# Bond.net
KiCad netlist of a schematic drawn in EAGLE
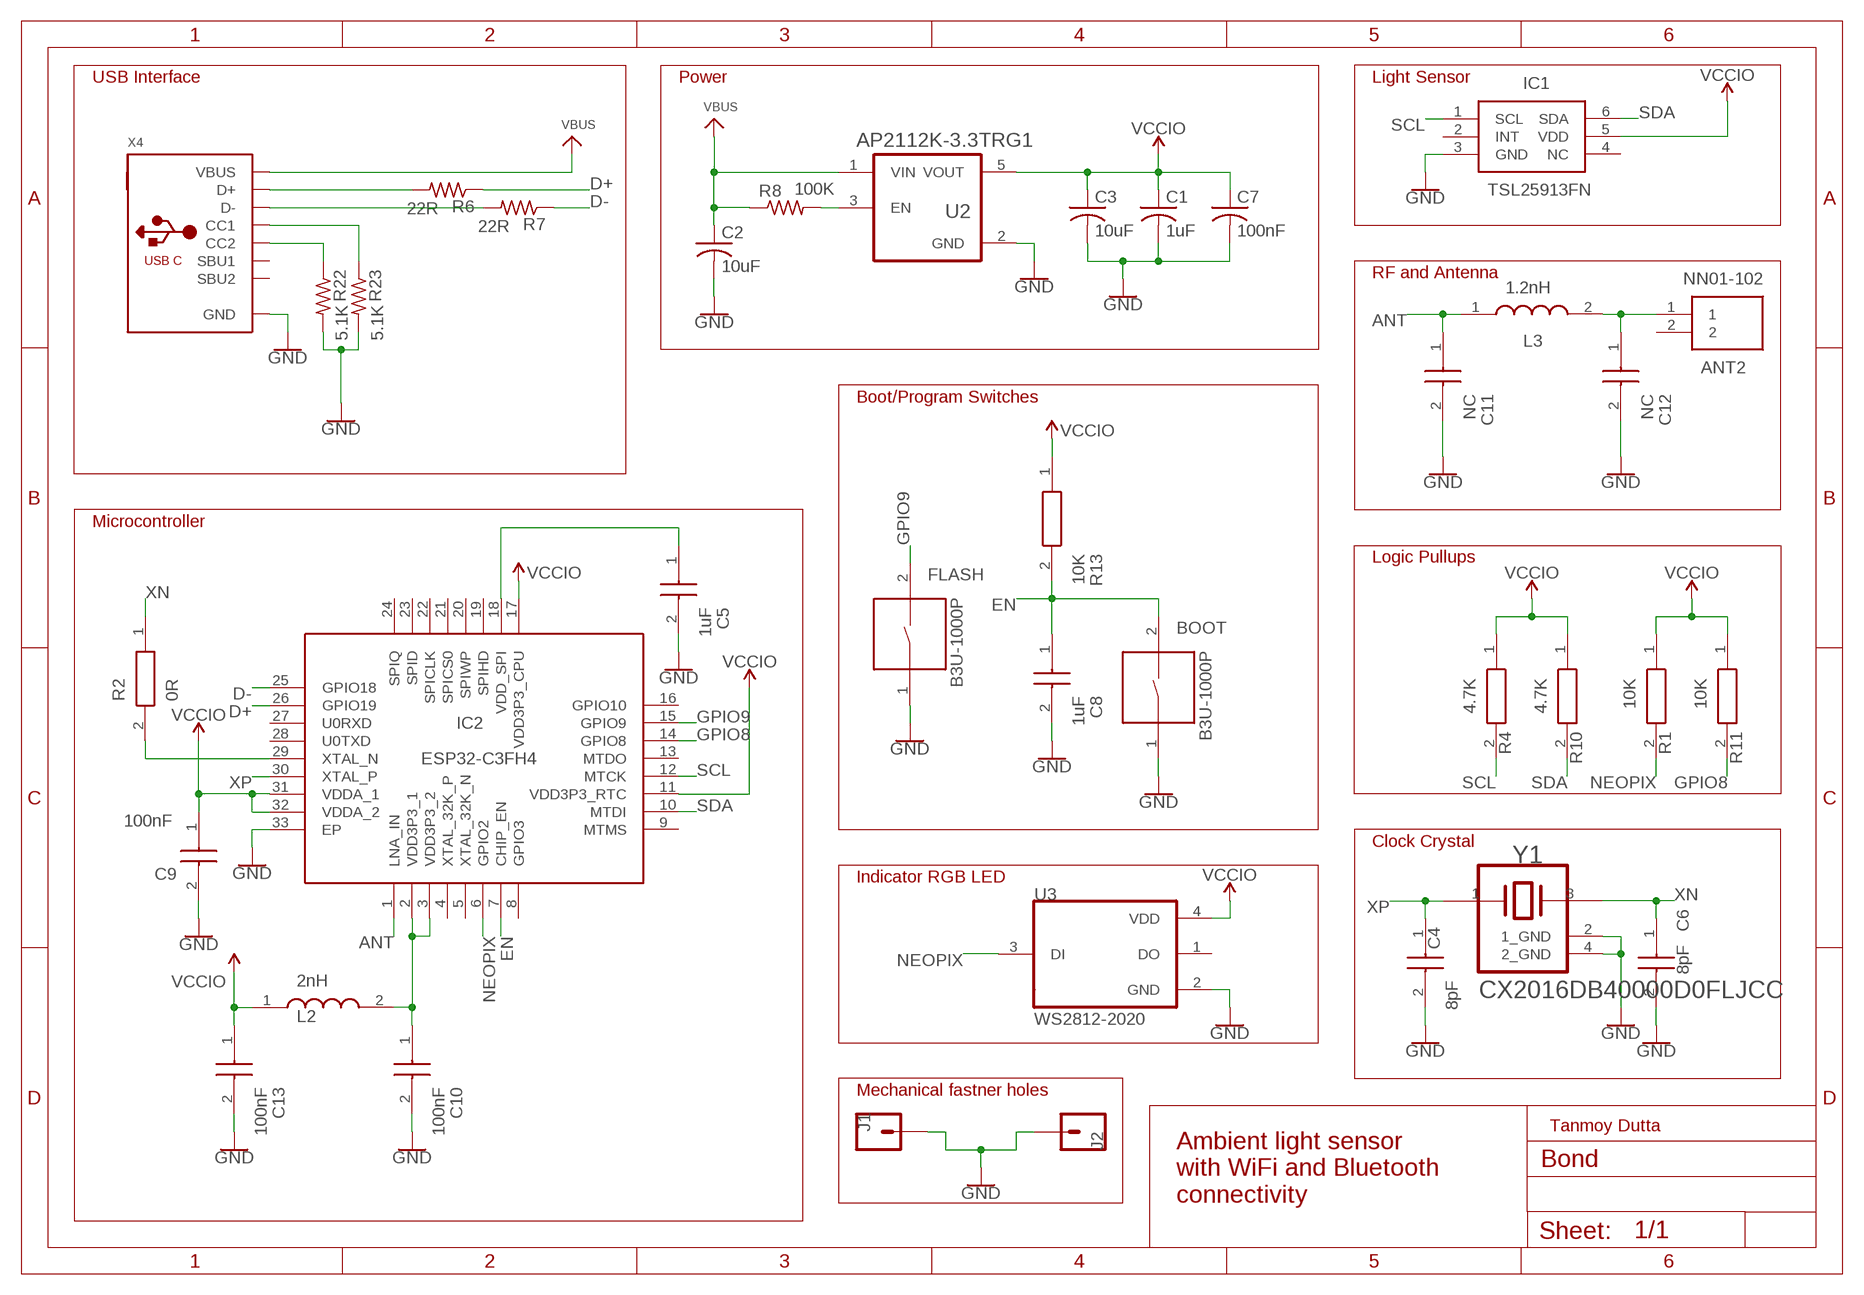
[diagram p0: schematic, sheet 1]

(export (version "E")
  (design (tool "Eeschema 10.0.6"))
  (components
    (comp (ref "ANT2")
      (value "NN01-102")
      (footprint "eagle-import:NN01102")
      (fields (field (name "MOUSER_PART_NUMBER") "128-NN01-102"))
      (libsource (lib "eagle-import") (part "NN01-102"))
    )
    (comp (ref "BOOT")
      (value "B3U-1000P")
      (footprint "eagle-import:SW_B3U-1000P")
      (fields (field (name "MF") "Omron"))
      (libsource (lib "eagle-import") (part "B3U-1000P"))
    )
    (comp (ref "C1")
      (value "1uF")
      (footprint "eagle-import:C0402")
      (fields (field (name "SPICEPREFIX") "C"))
      (libsource (lib "eagle-import") (part "C-USC0402"))
    )
    (comp (ref "C2")
      (value "10uF")
      (footprint "eagle-import:C0402")
      (fields (field (name "SPICEPREFIX") "C"))
      (libsource (lib "eagle-import") (part "C-USC0402"))
    )
    (comp (ref "C3")
      (value "10uF")
      (footprint "eagle-import:C0402")
      (fields (field (name "SPICEPREFIX") "C"))
      (libsource (lib "eagle-import") (part "C-USC0402"))
    )
    (comp (ref "C4")
      (value "8pF")
      (footprint "eagle-import:CAPC1005X55N")
      (fields
        (field (name "MANUFACTURER_PART_NUMBER") "GJM1555C1H120JB01J")
        (field (name "MOUSER_PART_NUMBER") "81-GJM1555C1H120JB1J")
      )
      (libsource (lib "eagle-import") (part "GJM1555C1H120JB01J"))
    )
    (comp (ref "C5")
      (value "1uF")
      (footprint "eagle-import:CAPC1005X55N")
      (fields
        (field (name "MANUFACTURER_PART_NUMBER") "GJM1555C1H120JB01J")
        (field (name "MOUSER_PART_NUMBER") "81-GJM1555C1H120JB1J")
      )
      (libsource (lib "eagle-import") (part "GJM1555C1H120JB01J"))
    )
    (comp (ref "C6")
      (value "8pF")
      (footprint "eagle-import:CAPC1005X55N")
      (fields
        (field (name "MANUFACTURER_PART_NUMBER") "GJM1555C1H120JB01J")
        (field (name "MOUSER_PART_NUMBER") "81-GJM1555C1H120JB1J")
      )
      (libsource (lib "eagle-import") (part "GJM1555C1H120JB01J"))
    )
    (comp (ref "C7")
      (value "100nF")
      (footprint "eagle-import:C0402")
      (fields (field (name "SPICEPREFIX") "C"))
      (libsource (lib "eagle-import") (part "C-USC0402"))
    )
    (comp (ref "C8")
      (value "1uF")
      (footprint "eagle-import:CAPC1005X55N")
      (fields
        (field (name "MANUFACTURER_PART_NUMBER") "GJM1555C1H120JB01J")
        (field (name "MOUSER_PART_NUMBER") "81-GJM1555C1H120JB1J")
      )
      (libsource (lib "eagle-import") (part "GJM1555C1H120JB01J"))
    )
    (comp (ref "C9")
      (value "100nF")
      (footprint "eagle-import:CAPC1005X55N")
      (fields
        (field (name "MANUFACTURER_PART_NUMBER") "GJM1555C1H120JB01J")
        (field (name "MOUSER_PART_NUMBER") "81-GJM1555C1H120JB1J")
      )
      (libsource (lib "eagle-import") (part "GJM1555C1H120JB01J"))
    )
    (comp (ref "C10")
      (value "100nF")
      (footprint "eagle-import:CAPC1005X55N")
      (fields
        (field (name "MANUFACTURER_PART_NUMBER") "GJM1555C1H120JB01J")
        (field (name "MOUSER_PART_NUMBER") "81-GJM1555C1H120JB1J")
      )
      (libsource (lib "eagle-import") (part "GJM1555C1H120JB01J"))
    )
    (comp (ref "C11")
      (value "NC")
      (footprint "eagle-import:CAPC1005X55N")
      (fields
        (field (name "MANUFACTURER_PART_NUMBER") "GJM1555C1H120JB01J")
        (field (name "MOUSER_PART_NUMBER") "81-GJM1555C1H120JB1J")
      )
      (libsource (lib "eagle-import") (part "GJM1555C1H120JB01J"))
    )
    (comp (ref "C12")
      (value "NC")
      (footprint "eagle-import:CAPC1005X55N")
      (fields
        (field (name "MANUFACTURER_PART_NUMBER") "GJM1555C1H120JB01J")
        (field (name "MOUSER_PART_NUMBER") "81-GJM1555C1H120JB1J")
      )
      (libsource (lib "eagle-import") (part "GJM1555C1H120JB01J"))
    )
    (comp (ref "C13")
      (value "100nF")
      (footprint "eagle-import:CAPC1005X55N")
      (fields
        (field (name "MANUFACTURER_PART_NUMBER") "GJM1555C1H120JB01J")
        (field (name "MOUSER_PART_NUMBER") "81-GJM1555C1H120JB1J")
      )
      (libsource (lib "eagle-import") (part "GJM1555C1H120JB01J"))
    )
    (comp (ref "FLASH")
      (value "B3U-1000P")
      (footprint "eagle-import:SW_B3U-1000P")
      (fields (field (name "MF") "Omron"))
      (libsource (lib "eagle-import") (part "B3U-1000P"))
    )
    (comp (ref "IC1")
      (value "TSL25913FN")
      (footprint "eagle-import:TSL25913FN")
      (fields (field (name "MOUSER_PART_NUMBER") "985-TSL25913FN") (field (name "SPICEPREFIX") "X"))
      (libsource (lib "eagle-import") (part "TSL25913FN"))
    )
    (comp (ref "IC2")
      (value "ESP32-C3FH4")
      (footprint "eagle-import:QFN50P500X500X90-33N")
      (fields (field (name "MOUSER_PART_NUMBER") "356-ESP32-C3FH4"))
      (libsource (lib "eagle-import") (part "ESP32-C3FH4"))
    )
    (comp (ref "J1")
      (value "CONN_01PTH_2MM")
      (footprint "eagle-import:1X01_2MM")
      (libsource (lib "eagle-import") (part "CONN_01PTH_2MM"))
    )
    (comp (ref "J2")
      (value "CONN_01PTH_2MM")
      (footprint "eagle-import:1X01_2MM")
      (libsource (lib "eagle-import") (part "CONN_01PTH_2MM"))
    )
    (comp (ref "L2")
      (value "2nH")
      (footprint "eagle-import:LQG15WH0N7B02D")
      (fields
        (field (name "ARROW_PART_NUMBER") "LQG15HH2N0S02D")
        (field (name "MOUSER_PART_NUMBER") "81-LQG15HH2N0S02D")
      )
      (libsource (lib "eagle-import") (part "LQG15HH2N0S02D"))
    )
    (comp (ref "L3")
      (value "1.2nH")
      (footprint "eagle-import:LQW15CNR20J00B")
      (fields (field (name "MANUFACTURER_PART_NUMBER") "LQW15AN1N6C0ZD"))
      (libsource (lib "eagle-import") (part "LQW15AN1N6C0ZD"))
    )
    (comp (ref "R1")
      (value "10K")
      (footprint "eagle-import:RESC1005X40N")
      (fields
        (field (name "ARROW_PART_NUMBER") "CRCW04020000Z0EE")
        (field (name "MOUSER_PART_NUMBER") "71-CRCW04020000Z0EE")
      )
      (libsource (lib "eagle-import") (part "CRCW04020000Z0EE"))
    )
    (comp (ref "R2")
      (value "0R")
      (footprint "eagle-import:RESC1005X40N")
      (fields
        (field (name "ARROW_PART_NUMBER") "CRCW04020000Z0EE")
        (field (name "MOUSER_PART_NUMBER") "71-CRCW04020000Z0EE")
      )
      (libsource (lib "eagle-import") (part "CRCW04020000Z0EE"))
    )
    (comp (ref "R4")
      (value "4.7K")
      (footprint "eagle-import:RESC1005X40N")
      (fields
        (field (name "ARROW_PART_NUMBER") "CRCW04020000Z0EE")
        (field (name "MOUSER_PART_NUMBER") "71-CRCW04020000Z0EE")
      )
      (libsource (lib "eagle-import") (part "CRCW04020000Z0EE"))
    )
    (comp (ref "R6")
      (value "22R")
      (footprint "eagle-import:R0402")
      (fields (field (name "SPICEPREFIX") "R"))
      (libsource (lib "eagle-import") (part "R-US_R0402"))
    )
    (comp (ref "R7")
      (value "22R")
      (footprint "eagle-import:R0402")
      (fields (field (name "SPICEPREFIX") "R"))
      (libsource (lib "eagle-import") (part "R-US_R0402"))
    )
    (comp (ref "R8")
      (value "100K")
      (footprint "eagle-import:R0402")
      (fields (field (name "SPICEPREFIX") "R"))
      (libsource (lib "eagle-import") (part "R-US_R0402"))
    )
    (comp (ref "R10")
      (value "4.7K")
      (footprint "eagle-import:RESC1005X40N")
      (fields
        (field (name "ARROW_PART_NUMBER") "CRCW04020000Z0EE")
        (field (name "MOUSER_PART_NUMBER") "71-CRCW04020000Z0EE")
      )
      (libsource (lib "eagle-import") (part "CRCW04020000Z0EE"))
    )
    (comp (ref "R11")
      (value "10K")
      (footprint "eagle-import:RESC1005X40N")
      (fields
        (field (name "ARROW_PART_NUMBER") "CRCW04020000Z0EE")
        (field (name "MOUSER_PART_NUMBER") "71-CRCW04020000Z0EE")
      )
      (libsource (lib "eagle-import") (part "CRCW04020000Z0EE"))
    )
    (comp (ref "R13")
      (value "10K")
      (footprint "eagle-import:RESC1005X40N")
      (fields
        (field (name "ARROW_PART_NUMBER") "CRCW04020000Z0EE")
        (field (name "MOUSER_PART_NUMBER") "71-CRCW04020000Z0EE")
      )
      (libsource (lib "eagle-import") (part "CRCW04020000Z0EE"))
    )
    (comp (ref "R22")
      (value "5.1K")
      (footprint "eagle-import:R0402")
      (fields (field (name "SPICEPREFIX") "R"))
      (libsource (lib "eagle-import") (part "R-US_R0402"))
    )
    (comp (ref "R23")
      (value "5.1K")
      (footprint "eagle-import:R0402")
      (fields (field (name "SPICEPREFIX") "R"))
      (libsource (lib "eagle-import") (part "R-US_R0402"))
    )
    (comp (ref "U2")
      (value "AP2112K-3.3TRG1")
      (footprint "eagle-import:SOT95P285X140-5N")
      (fields (field (name "MF") "Diodes Inc.") (field (name "SPICEPREFIX") "E"))
      (libsource (lib "eagle-import") (part "AP2112K-3.3TRG1"))
    )
    (comp (ref "U3")
      (value "WS2812-2020")
      (footprint "eagle-import:LED_WS2812-2020")
      (fields (field (name "MF") "Worldsemi"))
      (libsource (lib "eagle-import") (part "WS2812-2020"))
    )
    (comp (ref "X4")
      (value "MICROBUILDER_USB_C")
      (footprint "eagle-import:MICROBUILDER_USB_C_CUSB31-CFM2AX-01-X")
      (fields (field (name "SPICEPREFIX") "X"))
      (libsource (lib "eagle-import") (part "MICROBUILDER_USB_C"))
    )
    (comp (ref "Y1")
      (value "40MHz")
      (footprint "eagle-import:KYOCERA_INTERNATIONAL_INC._ELECTRONIC_COMPONENTS_CX2016DB40000D0FLJCC_0")
      (fields
        (field (name "DIGIKEY_PART_NUMBER") "1253-1120-1-ND")
        (field (name "MF") "Kyocera International Inc. Electronic Components")
        (field (name "MOUSER_PART_NUMBER") "581-CX2016DB40DFLJCC")
      )
      (libsource (lib "eagle-import") (part "KYOCERA_INTERNATIONAL_INC._ELECTRONIC_COMPONENTS_CX2016DB40000D0FLJCCKYOCERA_INTERNATIONAL_INC._ELECTRONIC_COMPONENTS_CX2016DB40000D0FLJCC_0_0"))
    )
  )
  (nets
    (net (code "1") (name "/ANT") (class "Default")
      (node (ref "C11") (pin "1") (pinfunction "1_1") (pintype "bidirectional"))
      (node (ref "IC2") (pin "1") (pinfunction "LNA_IN_1") (pintype "bidirectional"))
      (node (ref "L3") (pin "1") (pinfunction "1_1") (pintype "bidirectional"))
    )
    (net (code "2") (name "/D+") (class "Default")
      (node (ref "IC2") (pin "26") (pinfunction "GPIO19_26") (pintype "bidirectional"))
      (node (ref "R6") (pin "1") (pinfunction "1_1") (pintype "passive"))
    )
    (net (code "3") (name "/D-") (class "Default")
      (node (ref "IC2") (pin "25") (pinfunction "GPIO18_25") (pintype "bidirectional"))
      (node (ref "R7") (pin "1") (pinfunction "1_1") (pintype "passive"))
    )
    (net (code "4") (name "/EN") (class "Default")
      (node (ref "BOOT") (pin "2") (pinfunction "2_2") (pintype "passive"))
      (node (ref "C8") (pin "1") (pinfunction "1_1") (pintype "bidirectional"))
      (node (ref "IC2") (pin "7") (pinfunction "CHIP_EN_7") (pintype "bidirectional"))
      (node (ref "R13") (pin "2") (pinfunction "2_2") (pintype "bidirectional"))
    )
    (net (code "5") (name "/GPIO8") (class "Default")
      (node (ref "IC2") (pin "14") (pinfunction "GPIO8_14") (pintype "bidirectional"))
      (node (ref "R11") (pin "2") (pinfunction "2_2") (pintype "bidirectional"))
    )
    (net (code "6") (name "/GPIO9") (class "Default")
      (node (ref "FLASH") (pin "2") (pinfunction "2_2") (pintype "passive"))
      (node (ref "IC2") (pin "15") (pinfunction "GPIO9_15") (pintype "bidirectional"))
    )
    (net (code "7") (name "/NEOPIX") (class "Default")
      (node (ref "IC2") (pin "6") (pinfunction "GPIO2_6") (pintype "bidirectional"))
      (node (ref "R1") (pin "2") (pinfunction "2_2") (pintype "bidirectional"))
      (node (ref "U3") (pin "3") (pinfunction "DI_3") (pintype "input"))
    )
    (net (code "8") (name "/SCL") (class "Default")
      (node (ref "IC1") (pin "1") (pinfunction "SCL_1") (pintype "bidirectional"))
      (node (ref "IC2") (pin "12") (pinfunction "MTCK_12") (pintype "bidirectional"))
      (node (ref "R4") (pin "2") (pinfunction "2_2") (pintype "bidirectional"))
    )
    (net (code "9") (name "/SDA") (class "Default")
      (node (ref "IC1") (pin "6") (pinfunction "SDA_6") (pintype "bidirectional"))
      (node (ref "IC2") (pin "10") (pinfunction "MTDI_10") (pintype "bidirectional"))
      (node (ref "R10") (pin "2") (pinfunction "2_2") (pintype "bidirectional"))
    )
    (net (code "10") (name "/XN") (class "Default")
      (node (ref "C6") (pin "1") (pinfunction "1_1") (pintype "bidirectional"))
      (node (ref "R2") (pin "1") (pinfunction "1_1") (pintype "bidirectional"))
      (node (ref "Y1") (pin "3") (pinfunction "3_3") (pintype "passive"))
    )
    (net (code "11") (name "/XP") (class "Default")
      (node (ref "C4") (pin "1") (pinfunction "1_1") (pintype "bidirectional"))
      (node (ref "IC2") (pin "30") (pinfunction "XTAL_P_30") (pintype "bidirectional"))
      (node (ref "Y1") (pin "1") (pinfunction "1_1") (pintype "passive"))
    )
    (net (code "12") (name "GND") (class "Default")
      (node (ref "BOOT") (pin "1") (pinfunction "1_1") (pintype "passive"))
      (node (ref "C1") (pin "2") (pinfunction "2_2") (pintype "passive"))
      (node (ref "C10") (pin "2") (pinfunction "2_2") (pintype "bidirectional"))
      (node (ref "C11") (pin "2") (pinfunction "2_2") (pintype "bidirectional"))
      (node (ref "C12") (pin "2") (pinfunction "2_2") (pintype "bidirectional"))
      (node (ref "C13") (pin "2") (pinfunction "2_2") (pintype "bidirectional"))
      (node (ref "C2") (pin "2") (pinfunction "2_2") (pintype "passive"))
      (node (ref "C3") (pin "2") (pinfunction "2_2") (pintype "passive"))
      (node (ref "C4") (pin "2") (pinfunction "2_2") (pintype "bidirectional"))
      (node (ref "C5") (pin "2") (pinfunction "2_2") (pintype "bidirectional"))
      (node (ref "C6") (pin "2") (pinfunction "2_2") (pintype "bidirectional"))
      (node (ref "C7") (pin "2") (pinfunction "2_2") (pintype "passive"))
      (node (ref "C8") (pin "2") (pinfunction "2_2") (pintype "bidirectional"))
      (node (ref "C9") (pin "2") (pinfunction "2_2") (pintype "bidirectional"))
      (node (ref "FLASH") (pin "1") (pinfunction "1_1") (pintype "passive"))
      (node (ref "IC1") (pin "3") (pinfunction "GND_3") (pintype "bidirectional"))
      (node (ref "IC2") (pin "33") (pinfunction "EP_33") (pintype "bidirectional"))
      (node (ref "J1") (pin "1") (pinfunction "1_1") (pintype "passive"))
      (node (ref "J2") (pin "1") (pinfunction "1_1") (pintype "passive"))
      (node (ref "R22") (pin "2") (pinfunction "2_2") (pintype "passive"))
      (node (ref "R23") (pin "2") (pinfunction "2_2") (pintype "passive"))
      (node (ref "U2") (pin "2") (pinfunction "GND_2") (pintype "power_in"))
      (node (ref "U3") (pin "2") (pinfunction "GND_2") (pintype "power_in"))
      (node (ref "X4") (pin "A1B12") (pinfunction "GND_A1B12") (pintype "power_in"))
      (node (ref "X4") (pin "B1A12") (pinfunction "GND_B1A12") (pintype "power_in"))
      (node (ref "Y1") (pin "2") (pinfunction "1_GND_2") (pintype "power_in"))
      (node (ref "Y1") (pin "4") (pinfunction "2_GND_4") (pintype "power_in"))
    )
    (net (code "13") (name "Net-(ANT2-Pad1)") (class "Default")
      (node (ref "ANT2") (pin "1") (pinfunction "1_1") (pintype "bidirectional"))
      (node (ref "C12") (pin "1") (pinfunction "1_1") (pintype "bidirectional"))
      (node (ref "L3") (pin "2") (pinfunction "2_2") (pintype "bidirectional"))
    )
    (net (code "14") (name "Net-(IC2-VDD3P3_1)") (class "Default")
      (node (ref "C10") (pin "1") (pinfunction "1_1") (pintype "bidirectional"))
      (node (ref "IC2") (pin "2") (pinfunction "VDD3P3_1_2") (pintype "bidirectional"))
      (node (ref "IC2") (pin "3") (pinfunction "VDD3P3_2_3") (pintype "bidirectional"))
      (node (ref "L2") (pin "2") (pinfunction "2_2") (pintype "bidirectional"))
    )
    (net (code "15") (name "Net-(IC2-VDD_SPI)") (class "Default")
      (node (ref "C5") (pin "1") (pinfunction "1_1") (pintype "bidirectional"))
      (node (ref "IC2") (pin "18") (pinfunction "VDD_SPI_18") (pintype "bidirectional"))
    )
    (net (code "16") (name "Net-(IC2-XTAL_N)") (class "Default")
      (node (ref "IC2") (pin "29") (pinfunction "XTAL_N_29") (pintype "bidirectional"))
      (node (ref "R2") (pin "2") (pinfunction "2_2") (pintype "bidirectional"))
    )
    (net (code "17") (name "Net-(R6-Pad2)") (class "Default")
      (node (ref "R6") (pin "2") (pinfunction "2_2") (pintype "passive"))
      (node (ref "X4") (pin "A6") (pinfunction "D+_A6") (pintype "bidirectional"))
      (node (ref "X4") (pin "B6") (pinfunction "D+_B6") (pintype "bidirectional"))
    )
    (net (code "18") (name "Net-(R7-Pad2)") (class "Default")
      (node (ref "R7") (pin "2") (pinfunction "2_2") (pintype "passive"))
      (node (ref "X4") (pin "A7") (pinfunction "D-_A7") (pintype "bidirectional"))
      (node (ref "X4") (pin "B7") (pinfunction "D-_B7") (pintype "bidirectional"))
    )
    (net (code "19") (name "Net-(U2-EN)") (class "Default")
      (node (ref "R8") (pin "2") (pinfunction "2_2") (pintype "passive"))
      (node (ref "U2") (pin "3") (pinfunction "EN_3") (pintype "input"))
    )
    (net (code "20") (name "Net-(X4-CC1)") (class "Default")
      (node (ref "R23") (pin "1") (pinfunction "1_1") (pintype "passive"))
      (node (ref "X4") (pin "A5") (pinfunction "CC1_A5") (pintype "bidirectional"))
    )
    (net (code "21") (name "Net-(X4-CC2)") (class "Default")
      (node (ref "R22") (pin "1") (pinfunction "1_1") (pintype "passive"))
      (node (ref "X4") (pin "B5") (pinfunction "CC2_B5") (pintype "bidirectional"))
    )
    (net (code "22") (name "VBUS") (class "Default")
      (node (ref "C2") (pin "1") (pinfunction "1_1") (pintype "passive"))
      (node (ref "R8") (pin "1") (pinfunction "1_1") (pintype "passive"))
      (node (ref "U2") (pin "1") (pinfunction "VIN_1") (pintype "power_in"))
      (node (ref "X4") (pin "A4B9") (pinfunction "VBUS_A4B9") (pintype "power_in"))
      (node (ref "X4") (pin "B4A9") (pinfunction "VBUS_B4A9") (pintype "power_in"))
    )
    (net (code "23") (name "VCCIO") (class "Default")
      (node (ref "C1") (pin "1") (pinfunction "1_1") (pintype "passive"))
      (node (ref "C13") (pin "1") (pinfunction "1_1") (pintype "bidirectional"))
      (node (ref "C3") (pin "1") (pinfunction "1_1") (pintype "passive"))
      (node (ref "C7") (pin "1") (pinfunction "1_1") (pintype "passive"))
      (node (ref "C9") (pin "1") (pinfunction "1_1") (pintype "bidirectional"))
      (node (ref "IC1") (pin "5") (pinfunction "VDD_5") (pintype "bidirectional"))
      (node (ref "IC2") (pin "11") (pinfunction "VDD3P3_RTC_11") (pintype "bidirectional"))
      (node (ref "IC2") (pin "17") (pinfunction "VDD3P3_CPU_17") (pintype "bidirectional"))
      (node (ref "IC2") (pin "31") (pinfunction "VDDA_1_31") (pintype "bidirectional"))
      (node (ref "IC2") (pin "32") (pinfunction "VDDA_2_32") (pintype "bidirectional"))
      (node (ref "L2") (pin "1") (pinfunction "1_1") (pintype "bidirectional"))
      (node (ref "R1") (pin "1") (pinfunction "1_1") (pintype "bidirectional"))
      (node (ref "R10") (pin "1") (pinfunction "1_1") (pintype "bidirectional"))
      (node (ref "R11") (pin "1") (pinfunction "1_1") (pintype "bidirectional"))
      (node (ref "R13") (pin "1") (pinfunction "1_1") (pintype "bidirectional"))
      (node (ref "R4") (pin "1") (pinfunction "1_1") (pintype "bidirectional"))
      (node (ref "U2") (pin "5") (pinfunction "VOUT_5") (pintype "power_in"))
      (node (ref "U3") (pin "4") (pinfunction "VDD_4") (pintype "power_in"))
    )
    (net (code "24") (name "unconnected-(ANT2-Pad2)") (class "Default")
      (node (ref "ANT2") (pin "2") (pinfunction "2_2") (pintype "bidirectional"))
    )
    (net (code "25") (name "unconnected-(IC1-INT-Pad2)") (class "Default")
      (node (ref "IC1") (pin "2") (pinfunction "INT_2") (pintype "bidirectional"))
    )
    (net (code "26") (name "unconnected-(IC1-NC-Pad4)") (class "Default")
      (node (ref "IC1") (pin "4") (pinfunction "NC_4") (pintype "no_connect"))
    )
    (net (code "27") (name "unconnected-(IC2-GPIO3-Pad8)") (class "Default")
      (node (ref "IC2") (pin "8") (pinfunction "GPIO3_8") (pintype "bidirectional"))
    )
    (net (code "28") (name "unconnected-(IC2-GPIO10-Pad16)") (class "Default")
      (node (ref "IC2") (pin "16") (pinfunction "GPIO10_16") (pintype "bidirectional"))
    )
    (net (code "29") (name "unconnected-(IC2-MTDO-Pad13)") (class "Default")
      (node (ref "IC2") (pin "13") (pinfunction "MTDO_13") (pintype "bidirectional"))
    )
    (net (code "30") (name "unconnected-(IC2-MTMS-Pad9)") (class "Default")
      (node (ref "IC2") (pin "9") (pinfunction "MTMS_9") (pintype "bidirectional"))
    )
    (net (code "31") (name "unconnected-(IC2-SPICLK-Pad22)") (class "Default")
      (node (ref "IC2") (pin "22") (pinfunction "SPICLK_22") (pintype "bidirectional"))
    )
    (net (code "32") (name "unconnected-(IC2-SPICS0-Pad21)") (class "Default")
      (node (ref "IC2") (pin "21") (pinfunction "SPICS0_21") (pintype "bidirectional"))
    )
    (net (code "33") (name "unconnected-(IC2-SPID-Pad23)") (class "Default")
      (node (ref "IC2") (pin "23") (pinfunction "SPID_23") (pintype "bidirectional"))
    )
    (net (code "34") (name "unconnected-(IC2-SPIHD-Pad19)") (class "Default")
      (node (ref "IC2") (pin "19") (pinfunction "SPIHD_19") (pintype "bidirectional"))
    )
    (net (code "35") (name "unconnected-(IC2-SPIQ-Pad24)") (class "Default")
      (node (ref "IC2") (pin "24") (pinfunction "SPIQ_24") (pintype "bidirectional"))
    )
    (net (code "36") (name "unconnected-(IC2-SPIWP-Pad20)") (class "Default")
      (node (ref "IC2") (pin "20") (pinfunction "SPIWP_20") (pintype "bidirectional"))
    )
    (net (code "37") (name "unconnected-(IC2-U0RXD-Pad27)") (class "Default")
      (node (ref "IC2") (pin "27") (pinfunction "U0RXD_27") (pintype "bidirectional"))
    )
    (net (code "38") (name "unconnected-(IC2-U0TXD-Pad28)") (class "Default")
      (node (ref "IC2") (pin "28") (pinfunction "U0TXD_28") (pintype "bidirectional"))
    )
    (net (code "39") (name "unconnected-(IC2-XTAL_32K_N-Pad5)") (class "Default")
      (node (ref "IC2") (pin "5") (pinfunction "XTAL_32K_N_5") (pintype "bidirectional"))
    )
    (net (code "40") (name "unconnected-(IC2-XTAL_32K_P-Pad4)") (class "Default")
      (node (ref "IC2") (pin "4") (pinfunction "XTAL_32K_P_4") (pintype "bidirectional"))
    )
    (net (code "41") (name "unconnected-(U3-DO-Pad1)") (class "Default")
      (node (ref "U3") (pin "1") (pinfunction "DO_1") (pintype "output"))
    )
    (net (code "42") (name "unconnected-(X4-SBU1-PadA8)") (class "Default")
      (node (ref "X4") (pin "A8") (pinfunction "SBU1_A8") (pintype "bidirectional"))
    )
    (net (code "43") (name "unconnected-(X4-SBU2-PadB8)") (class "Default")
      (node (ref "X4") (pin "B8") (pinfunction "SBU2_B8") (pintype "bidirectional"))
    )
  )
)
